# SCH.net
KiCad netlist of a schematic drawn in EAGLE
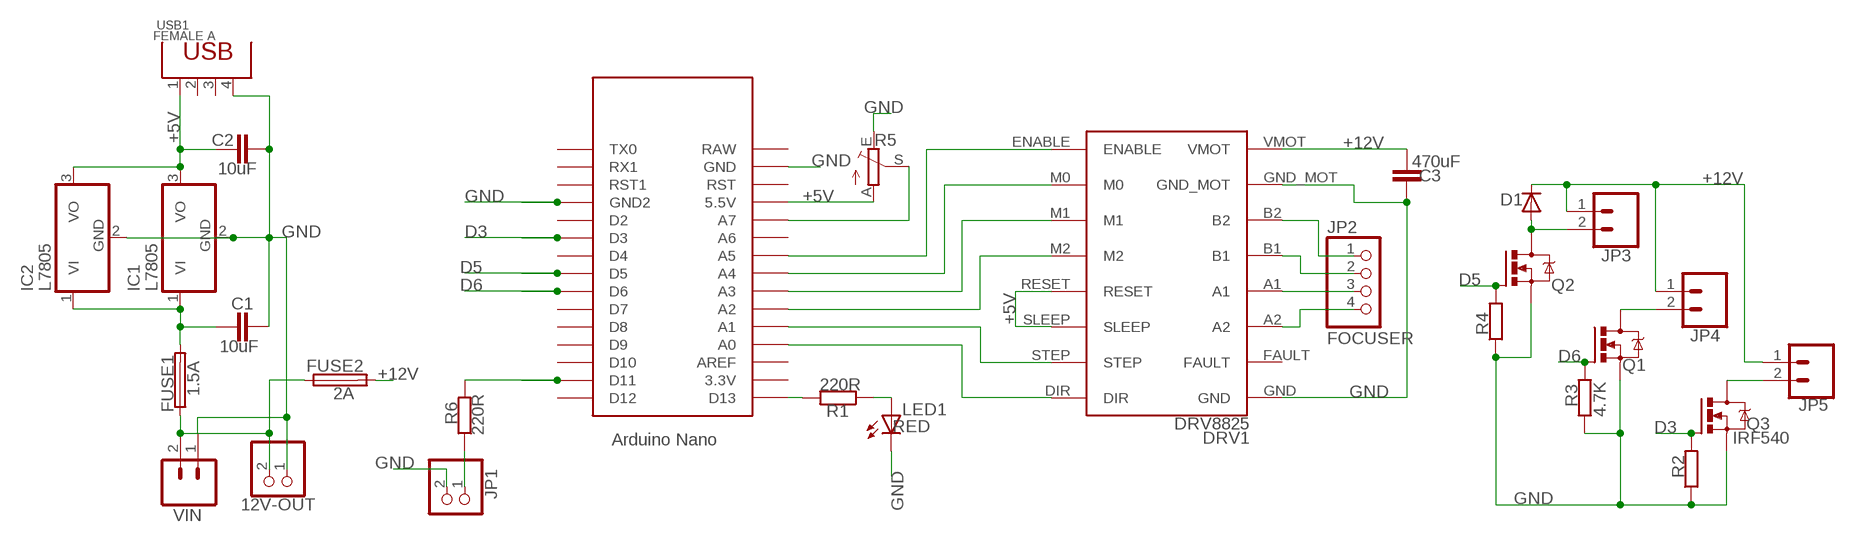
[diagram p0: schematic, sheet 1]

(export (version "E")
  (design (tool "Eeschema 10.0.6"))
  (components
    (comp (ref "12V-OUT")
      (value "PINHD-1X2")
      (footprint "eagle-import:1X02")
      (libsource (lib "eagle-import") (part "PINHD-1X2"))
    )
    (comp (ref "C1")
      (value "10uF")
      (footprint "eagle-import:C025-024X044")
      (libsource (lib "eagle-import") (part "C-EU025-024X044"))
    )
    (comp (ref "C2")
      (value "10uF")
      (footprint "eagle-import:C025-024X044")
      (libsource (lib "eagle-import") (part "C-EU025-024X044"))
    )
    (comp (ref "C3")
      (value "470uF")
      (footprint "eagle-import:C5B2.5")
      (fields (field (name "SPICEPREFIX") "C"))
      (libsource (lib "eagle-import") (part "C5/2.5"))
    )
    (comp (ref "D1")
      (value "DIODE-D-2.5")
      (footprint "eagle-import:D-2.5")
      (libsource (lib "eagle-import") (part "DIODE-D-2.5"))
    )
    (comp (ref "DRV1")
      (value "DRV8825")
      (footprint "eagle-import:DRV8825")
      (fields (field (name "SPICEPREFIX") "X"))
      (libsource (lib "eagle-import") (part "DRV8825"))
    )
    (comp (ref "FUSE1")
      (value "1.5A")
      (footprint "eagle-import:FUSE_HOLDER_5X20MM")
      (libsource (lib "eagle-import") (part "FUSEBLANK_5X20MM"))
    )
    (comp (ref "FUSE2")
      (value "2A")
      (footprint "eagle-import:FUSE_HOLDER_5X20MM")
      (libsource (lib "eagle-import") (part "FUSEBLANK_5X20MM"))
    )
    (comp (ref "IC1")
      (value "L7805")
      (footprint "eagle-import:TO220V")
      (libsource (lib "eagle-import") (part "78TV6"))
    )
    (comp (ref "IC2")
      (value "L7805")
      (footprint "eagle-import:TO220V")
      (libsource (lib "eagle-import") (part "78TV6"))
    )
    (comp (ref "JP1")
      (value "PINHD-1X2")
      (footprint "eagle-import:1X02")
      (fields (field (name "SPICEPREFIX") "B"))
      (libsource (lib "eagle-import") (part "PINHD-1X2"))
    )
    (comp (ref "JP2")
      (value "FOCUSER")
      (footprint "eagle-import:1X04")
      (fields (field (name "SPICEPREFIX") "E"))
      (libsource (lib "eagle-import") (part "PINHD-1X4"))
    )
    (comp (ref "JP3")
      (value "CONN_025MM")
      (footprint "eagle-import:SCREWTERMINAL-5MM-2")
      (libsource (lib "eagle-import") (part "CONN_025MM"))
    )
    (comp (ref "JP4")
      (value "CONN_025MM")
      (footprint "eagle-import:SCREWTERMINAL-5MM-2")
      (libsource (lib "eagle-import") (part "CONN_025MM"))
    )
    (comp (ref "JP5")
      (value "CONN_025MM")
      (footprint "eagle-import:SCREWTERMINAL-5MM-2")
      (fields (field (name "SPICEPREFIX") "H"))
      (libsource (lib "eagle-import") (part "CONN_025MM"))
    )
    (comp (ref "LED1")
      (value "RED")
      (footprint "eagle-import:LED3MM")
      (fields (field (name "SPICEPREFIX") "L"))
      (libsource (lib "eagle-import") (part "LED3MM"))
    )
    (comp (ref "Q1")
      (value "IRF540")
      (footprint "eagle-import:TO220BV")
      (libsource (lib "eagle-import") (part "IRF540"))
    )
    (comp (ref "Q2")
      (value "IRF540")
      (footprint "eagle-import:TO220BV")
      (libsource (lib "eagle-import") (part "IRF540"))
    )
    (comp (ref "Q3")
      (value "IRF540")
      (footprint "eagle-import:TO220BV")
      (libsource (lib "eagle-import") (part "IRF540"))
    )
    (comp (ref "R1")
      (value "220R")
      (footprint "eagle-import:0204_5")
      (fields (field (name "SPICEPREFIX") "R"))
      (libsource (lib "eagle-import") (part "resistor_348_R-EU_0204/5"))
    )
    (comp (ref "R2")
      (value "4.7K")
      (footprint "eagle-import:0204_5")
      (libsource (lib "eagle-import") (part "R-EU_0204/5"))
    )
    (comp (ref "R3")
      (value "4.7K")
      (footprint "eagle-import:0204_5")
      (libsource (lib "eagle-import") (part "R-EU_0204/5"))
    )
    (comp (ref "R4")
      (value "4.7K")
      (footprint "eagle-import:0204_5")
      (libsource (lib "eagle-import") (part "R-EU_0204/5"))
    )
    (comp (ref "R5")
      (value "TRIM_EU-B64Y")
      (footprint "eagle-import:B64Y")
      (fields (field (name "SPICEPREFIX") "J"))
      (libsource (lib "eagle-import") (part "TRIM_EU-B64Y"))
    )
    (comp (ref "R6")
      (value "220R")
      (footprint "eagle-import:0204_5")
      (fields (field (name "SPICEPREFIX") "R"))
      (libsource (lib "eagle-import") (part "resistor_348_R-EU_0204/5"))
    )
    (comp (ref "U$1")
      (value "NANO")
      (footprint "eagle-import:NANO")
      (libsource (lib "eagle-import") (part "NANO"))
    )
    (comp (ref "USB1")
      (value "FEMALE A")
      (footprint "eagle-import:USB4+2P-2.0-90D")
      (libsource (lib "eagle-import") (part "DIP-USB-A-TYPE-FMAL(4+2P-2.0-90D)"))
    )
    (comp (ref "VIN")
      (value "CONN_025MM")
      (footprint "eagle-import:SCREWTERMINAL-5MM-2")
      (libsource (lib "eagle-import") (part "CONN_025MM"))
    )
  )
  (nets
    (net (code "1") (name "/+5V") (class "Default")
      (node (ref "C2") (pin "1") (pinfunction "1_1") (pintype "passive"))
      (node (ref "DRV1") (pin "RESET") (pinfunction "RESET_RESET") (pintype "bidirectional"))
      (node (ref "DRV1") (pin "SLEEP") (pinfunction "SLEEP_SLEEP") (pintype "bidirectional"))
      (node (ref "IC1") (pin "3") (pinfunction "VO_3") (pintype "passive"))
      (node (ref "IC2") (pin "3") (pinfunction "VO_3") (pintype "passive"))
      (node (ref "R5") (pin "A") (pinfunction "A_A") (pintype "passive"))
      (node (ref "U$1") (pin "5V") (pinfunction "5.5V_5V") (pintype "bidirectional"))
      (node (ref "USB1") (pin "1") (pinfunction "1_1") (pintype "bidirectional"))
    )
    (net (code "2") (name "/+12V") (class "Default")
      (node (ref "C3") (pin "2") (pinfunction "2_2") (pintype "passive"))
      (node (ref "D1") (pin "C") (pinfunction "C_C") (pintype "passive"))
      (node (ref "DRV1") (pin "VMOT") (pinfunction "VMOT_VMOT") (pintype "bidirectional"))
      (node (ref "FUSE2") (pin "2") (pinfunction "2_2") (pintype "passive"))
      (node (ref "JP3") (pin "1") (pinfunction "1_1") (pintype "passive"))
      (node (ref "JP4") (pin "1") (pinfunction "1_1") (pintype "passive"))
      (node (ref "JP5") (pin "1") (pinfunction "1_1") (pintype "passive"))
    )
    (net (code "3") (name "/D3") (class "Default")
      (node (ref "Q3") (pin "G") (pinfunction "G_G") (pintype "passive"))
      (node (ref "R2") (pin "2") (pinfunction "2_2") (pintype "passive"))
      (node (ref "U$1") (pin "D3") (pinfunction "D3_D3") (pintype "bidirectional"))
    )
    (net (code "4") (name "/D5") (class "Default")
      (node (ref "Q2") (pin "G") (pinfunction "G_G") (pintype "passive"))
      (node (ref "R4") (pin "2") (pinfunction "2_2") (pintype "passive"))
      (node (ref "U$1") (pin "D5") (pinfunction "D5_D5") (pintype "bidirectional"))
    )
    (net (code "5") (name "/D6") (class "Default")
      (node (ref "Q1") (pin "G") (pinfunction "G_G") (pintype "passive"))
      (node (ref "R3") (pin "2") (pinfunction "2_2") (pintype "passive"))
      (node (ref "U$1") (pin "D6") (pinfunction "D6_D6") (pintype "bidirectional"))
    )
    (net (code "6") (name "/GND") (class "Default")
      (node (ref "12V-OUT") (pin "1") (pinfunction "1_1") (pintype "passive"))
      (node (ref "C1") (pin "2") (pinfunction "2_2") (pintype "passive"))
      (node (ref "C2") (pin "2") (pinfunction "2_2") (pintype "passive"))
      (node (ref "C3") (pin "1") (pinfunction "1_1") (pintype "passive"))
      (node (ref "DRV1") (pin "GND") (pinfunction "GND_GND") (pintype "bidirectional"))
      (node (ref "DRV1") (pin "GND_MOT") (pinfunction "GND_MOT_GND_MOT") (pintype "bidirectional"))
      (node (ref "IC1") (pin "2") (pinfunction "GND_2") (pintype "passive"))
      (node (ref "IC2") (pin "2") (pinfunction "GND_2") (pintype "passive"))
      (node (ref "JP1") (pin "2") (pinfunction "2_2") (pintype "passive"))
      (node (ref "LED1") (pin "K") (pinfunction "C_K") (pintype "passive"))
      (node (ref "Q1") (pin "S") (pinfunction "S_S") (pintype "passive"))
      (node (ref "Q2") (pin "S") (pinfunction "S_S") (pintype "passive"))
      (node (ref "Q3") (pin "S") (pinfunction "S_S") (pintype "passive"))
      (node (ref "R2") (pin "1") (pinfunction "1_1") (pintype "passive"))
      (node (ref "R3") (pin "1") (pinfunction "1_1") (pintype "passive"))
      (node (ref "R4") (pin "1") (pinfunction "1_1") (pintype "passive"))
      (node (ref "R5") (pin "E") (pinfunction "E_E") (pintype "passive"))
      (node (ref "U$1") (pin "GND") (pinfunction "GND_GND") (pintype "bidirectional"))
      (node (ref "U$1") (pin "GND1") (pinfunction "GND2_GND1") (pintype "bidirectional"))
      (node (ref "USB1") (pin "4") (pinfunction "4_4") (pintype "bidirectional"))
      (node (ref "VIN") (pin "1") (pinfunction "1_1") (pintype "passive"))
    )
    (net (code "7") (name "Net-(12V-OUT-Pad2)") (class "Default")
      (node (ref "12V-OUT") (pin "2") (pinfunction "2_2") (pintype "passive"))
      (node (ref "FUSE1") (pin "1") (pinfunction "1_1") (pintype "passive"))
      (node (ref "FUSE2") (pin "1") (pinfunction "1_1") (pintype "passive"))
      (node (ref "VIN") (pin "2") (pinfunction "2_2") (pintype "passive"))
    )
    (net (code "8") (name "Net-(D1-PadA)") (class "Default")
      (node (ref "D1") (pin "A") (pinfunction "A_A") (pintype "passive"))
      (node (ref "JP3") (pin "2") (pinfunction "2_2") (pintype "passive"))
      (node (ref "Q2") (pin "D") (pinfunction "D_D") (pintype "passive"))
    )
    (net (code "9") (name "Net-(DRV1-PadA1)") (class "Default")
      (node (ref "DRV1") (pin "A1") (pinfunction "A1_A1") (pintype "bidirectional"))
      (node (ref "JP2") (pin "3") (pinfunction "3_3") (pintype "passive"))
    )
    (net (code "10") (name "Net-(DRV1-PadA2)") (class "Default")
      (node (ref "DRV1") (pin "A2") (pinfunction "A2_A2") (pintype "bidirectional"))
      (node (ref "JP2") (pin "4") (pinfunction "4_4") (pintype "passive"))
    )
    (net (code "11") (name "Net-(DRV1-PadB1)") (class "Default")
      (node (ref "DRV1") (pin "B1") (pinfunction "B1_B1") (pintype "bidirectional"))
      (node (ref "JP2") (pin "2") (pinfunction "2_2") (pintype "passive"))
    )
    (net (code "12") (name "Net-(DRV1-PadB2)") (class "Default")
      (node (ref "DRV1") (pin "B2") (pinfunction "B2_B2") (pintype "bidirectional"))
      (node (ref "JP2") (pin "1") (pinfunction "1_1") (pintype "passive"))
    )
    (net (code "13") (name "Net-(DRV1-PadDIR)") (class "Default")
      (node (ref "DRV1") (pin "DIR") (pinfunction "DIR_DIR") (pintype "bidirectional"))
      (node (ref "U$1") (pin "A0") (pinfunction "A0_A0") (pintype "bidirectional"))
    )
    (net (code "14") (name "Net-(DRV1-PadENABLE)") (class "Default")
      (node (ref "DRV1") (pin "ENABLE") (pinfunction "ENABLE_ENABLE") (pintype "bidirectional"))
      (node (ref "U$1") (pin "A5") (pinfunction "A5_A5") (pintype "bidirectional"))
    )
    (net (code "15") (name "Net-(DRV1-PadM0)") (class "Default")
      (node (ref "DRV1") (pin "M0") (pinfunction "M0_M0") (pintype "bidirectional"))
      (node (ref "U$1") (pin "A4") (pinfunction "A4_A4") (pintype "bidirectional"))
    )
    (net (code "16") (name "Net-(DRV1-PadM1)") (class "Default")
      (node (ref "DRV1") (pin "M1") (pinfunction "M1_M1") (pintype "bidirectional"))
      (node (ref "U$1") (pin "A3") (pinfunction "A3_A3") (pintype "bidirectional"))
    )
    (net (code "17") (name "Net-(DRV1-PadM2)") (class "Default")
      (node (ref "DRV1") (pin "M2") (pinfunction "M2_M2") (pintype "bidirectional"))
      (node (ref "U$1") (pin "A2") (pinfunction "A2_A2") (pintype "bidirectional"))
    )
    (net (code "18") (name "Net-(DRV1-PadSTEP)") (class "Default")
      (node (ref "DRV1") (pin "STEP") (pinfunction "STEP_STEP") (pintype "bidirectional"))
      (node (ref "U$1") (pin "A1") (pinfunction "A1_A1") (pintype "bidirectional"))
    )
    (net (code "19") (name "Net-(IC1-VI)") (class "Default")
      (node (ref "C1") (pin "1") (pinfunction "1_1") (pintype "passive"))
      (node (ref "FUSE1") (pin "2") (pinfunction "2_2") (pintype "passive"))
      (node (ref "IC1") (pin "1") (pinfunction "VI_1") (pintype "input"))
      (node (ref "IC2") (pin "1") (pinfunction "VI_1") (pintype "input"))
    )
    (net (code "20") (name "Net-(JP1-Pad1)") (class "Default")
      (node (ref "JP1") (pin "1") (pinfunction "1_1") (pintype "passive"))
      (node (ref "R6") (pin "1") (pinfunction "1_1") (pintype "passive"))
    )
    (net (code "21") (name "Net-(JP4-Pad2)") (class "Default")
      (node (ref "JP4") (pin "2") (pinfunction "2_2") (pintype "passive"))
      (node (ref "Q1") (pin "D") (pinfunction "D_D") (pintype "passive"))
    )
    (net (code "22") (name "Net-(JP5-Pad2)") (class "Default")
      (node (ref "JP5") (pin "2") (pinfunction "2_2") (pintype "passive"))
      (node (ref "Q3") (pin "D") (pinfunction "D_D") (pintype "passive"))
    )
    (net (code "23") (name "Net-(LED1-PadA)") (class "Default")
      (node (ref "LED1") (pin "A") (pinfunction "A_A") (pintype "passive"))
      (node (ref "R1") (pin "1") (pinfunction "1_1") (pintype "passive"))
    )
    (net (code "24") (name "Net-(R1-Pad2)") (class "Default")
      (node (ref "R1") (pin "2") (pinfunction "2_2") (pintype "passive"))
      (node (ref "U$1") (pin "D13") (pinfunction "D13_D13") (pintype "bidirectional"))
    )
    (net (code "25") (name "Net-(R5-PadS)") (class "Default")
      (node (ref "R5") (pin "S") (pinfunction "S_S") (pintype "passive"))
      (node (ref "U$1") (pin "A7") (pinfunction "A7_A7") (pintype "bidirectional"))
    )
    (net (code "26") (name "Net-(R6-Pad2)") (class "Default")
      (node (ref "R6") (pin "2") (pinfunction "2_2") (pintype "passive"))
      (node (ref "U$1") (pin "D11") (pinfunction "D11_D11") (pintype "bidirectional"))
    )
    (net (code "27") (name "unconnected-(DRV1-PadFAULT)") (class "Default")
      (node (ref "DRV1") (pin "FAULT") (pinfunction "FAULT_FAULT") (pintype "bidirectional"))
    )
    (net (code "28") (name "unconnected-(U$1-Pad3.3V)") (class "Default")
      (node (ref "U$1") (pin "3.3V") (pinfunction "3.3V_3.3V") (pintype "bidirectional"))
    )
    (net (code "29") (name "unconnected-(U$1-PadA6)") (class "Default")
      (node (ref "U$1") (pin "A6") (pinfunction "A6_A6") (pintype "bidirectional"))
    )
    (net (code "30") (name "unconnected-(U$1-PadAREF)") (class "Default")
      (node (ref "U$1") (pin "AREF") (pinfunction "AREF_AREF") (pintype "bidirectional"))
    )
    (net (code "31") (name "unconnected-(U$1-PadD2)") (class "Default")
      (node (ref "U$1") (pin "D2") (pinfunction "D2_D2") (pintype "bidirectional"))
    )
    (net (code "32") (name "unconnected-(U$1-PadD4)") (class "Default")
      (node (ref "U$1") (pin "D4") (pinfunction "D4_D4") (pintype "bidirectional"))
    )
    (net (code "33") (name "unconnected-(U$1-PadD7)") (class "Default")
      (node (ref "U$1") (pin "D7") (pinfunction "D7_D7") (pintype "bidirectional"))
    )
    (net (code "34") (name "unconnected-(U$1-PadD8)") (class "Default")
      (node (ref "U$1") (pin "D8") (pinfunction "D8_D8") (pintype "bidirectional"))
    )
    (net (code "35") (name "unconnected-(U$1-PadD9)") (class "Default")
      (node (ref "U$1") (pin "D9") (pinfunction "D9_D9") (pintype "bidirectional"))
    )
    (net (code "36") (name "unconnected-(U$1-PadD10)") (class "Default")
      (node (ref "U$1") (pin "D10") (pinfunction "D10_D10") (pintype "bidirectional"))
    )
    (net (code "37") (name "unconnected-(U$1-PadD12)") (class "Default")
      (node (ref "U$1") (pin "D12") (pinfunction "D12_D12") (pintype "bidirectional"))
    )
    (net (code "38") (name "unconnected-(U$1-PadICSP1)") (class "Default")
      (node (ref "U$1") (pin "ICSP1") (pinfunction "ICSP1_ICSP1") (pintype "bidirectional"))
    )
    (net (code "39") (name "unconnected-(U$1-PadICSP2)") (class "Default")
      (node (ref "U$1") (pin "ICSP2") (pinfunction "ICSP2_ICSP2") (pintype "bidirectional"))
    )
    (net (code "40") (name "unconnected-(U$1-PadICSP3)") (class "Default")
      (node (ref "U$1") (pin "ICSP3") (pinfunction "ICSP3_ICSP3") (pintype "bidirectional"))
    )
    (net (code "41") (name "unconnected-(U$1-PadICSP4)") (class "Default")
      (node (ref "U$1") (pin "ICSP4") (pinfunction "ICSP4_ICSP4") (pintype "bidirectional"))
    )
    (net (code "42") (name "unconnected-(U$1-PadICSP5)") (class "Default")
      (node (ref "U$1") (pin "ICSP5") (pinfunction "ICSP5_ICSP5") (pintype "bidirectional"))
    )
    (net (code "43") (name "unconnected-(U$1-PadICSP6)") (class "Default")
      (node (ref "U$1") (pin "ICSP6") (pinfunction "ICSP6_ICSP6") (pintype "bidirectional"))
    )
    (net (code "44") (name "unconnected-(U$1-PadRAW)") (class "Default")
      (node (ref "U$1") (pin "RAW") (pinfunction "RAW_RAW") (pintype "bidirectional"))
    )
    (net (code "45") (name "unconnected-(U$1-PadRST)") (class "Default")
      (node (ref "U$1") (pin "RST") (pinfunction "RST_RST") (pintype "bidirectional"))
    )
    (net (code "46") (name "unconnected-(U$1-PadRST1)") (class "Default")
      (node (ref "U$1") (pin "RST1") (pinfunction "RST1_RST1") (pintype "bidirectional"))
    )
    (net (code "47") (name "unconnected-(U$1-PadRX1)") (class "Default")
      (node (ref "U$1") (pin "RX1") (pinfunction "RX1_RX1") (pintype "bidirectional"))
    )
    (net (code "48") (name "unconnected-(U$1-PadTX0)") (class "Default")
      (node (ref "U$1") (pin "TX0") (pinfunction "TX0_TX0") (pintype "bidirectional"))
    )
    (net (code "49") (name "unconnected-(USB1-Pad2)") (class "Default")
      (node (ref "USB1") (pin "2") (pinfunction "2_2") (pintype "bidirectional"))
    )
    (net (code "50") (name "unconnected-(USB1-Pad3)") (class "Default")
      (node (ref "USB1") (pin "3") (pinfunction "3_3") (pintype "bidirectional"))
    )
  )
)
